# padsSMD.net
KiCad netlist of a schematic drawn in EAGLE
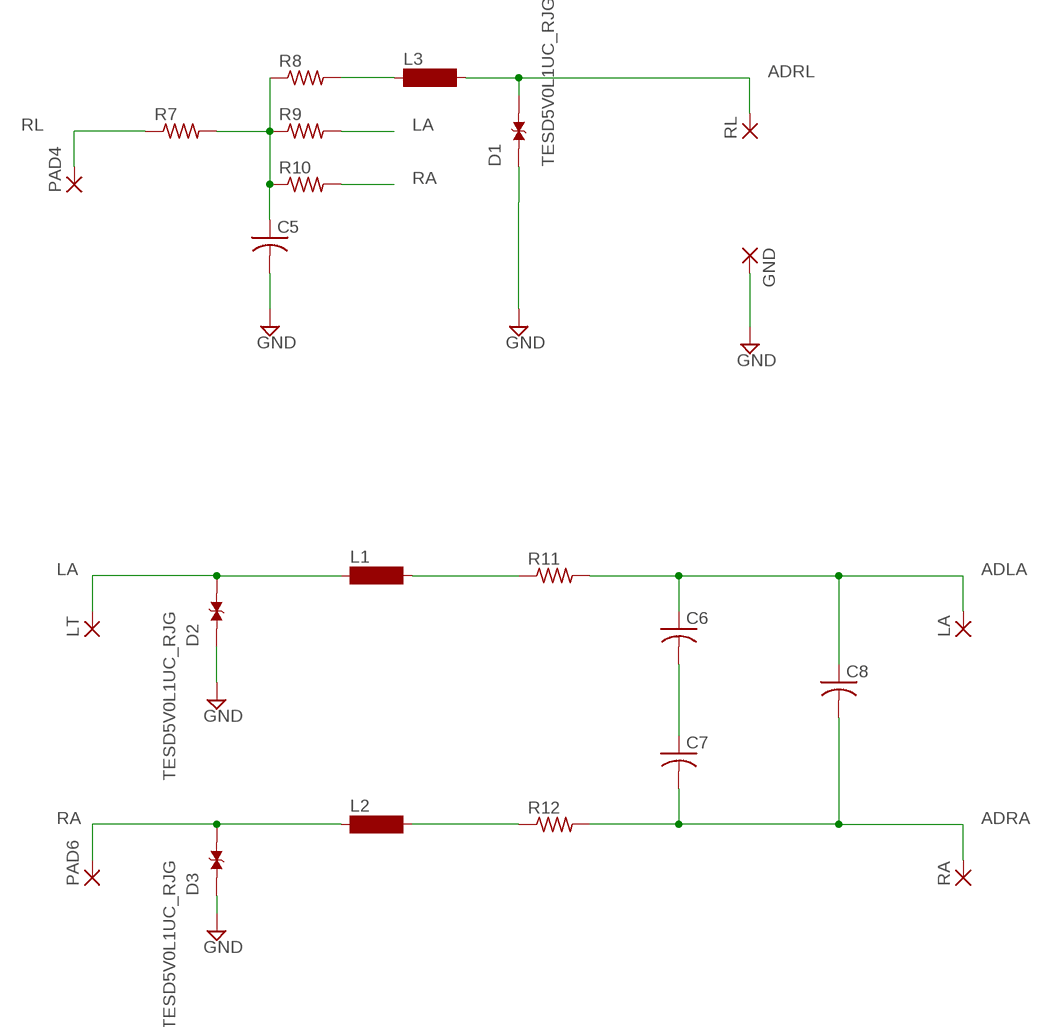
[diagram p0: schematic, sheet 1]

(export (version "E")
  (design (tool "Eeschema 10.0.6"))
  (components
    (comp (ref "C5")
      (value "C-USC1206")
      (footprint "eagle-import:C1206")
      (libsource (lib "eagle-import") (part "C-USC1206"))
    )
    (comp (ref "C6")
      (value "C-USC1206")
      (footprint "eagle-import:C1206")
      (libsource (lib "eagle-import") (part "C-USC1206"))
    )
    (comp (ref "C7")
      (value "C-USC1206")
      (footprint "eagle-import:C1206")
      (libsource (lib "eagle-import") (part "C-USC1206"))
    )
    (comp (ref "C8")
      (value "C-USC1206")
      (footprint "eagle-import:C1206")
      (libsource (lib "eagle-import") (part "C-USC1206"))
    )
    (comp (ref "D1")
      (value "TESD5V0L1UC_RJG")
      (footprint "eagle-import:DIO_TESD5V0L1UC_RJG")
      (fields (field (name "MF") "Taiwan Semiconductor Corporation") (field (name "MP") "TESD5V0L1UC RJG"))
      (libsource (lib "eagle-import") (part "TESD5V0L1UC_RJG"))
    )
    (comp (ref "D2")
      (value "TESD5V0L1UC_RJG")
      (footprint "eagle-import:DIO_TESD5V0L1UC_RJG")
      (fields (field (name "MF") "Taiwan Semiconductor Corporation") (field (name "MP") "TESD5V0L1UC RJG"))
      (libsource (lib "eagle-import") (part "TESD5V0L1UC_RJG"))
    )
    (comp (ref "D3")
      (value "TESD5V0L1UC_RJG")
      (footprint "eagle-import:DIO_TESD5V0L1UC_RJG")
      (fields (field (name "MF") "Taiwan Semiconductor Corporation") (field (name "MP") "TESD5V0L1UC RJG"))
      (libsource (lib "eagle-import") (part "TESD5V0L1UC_RJG"))
    )
    (comp (ref "GND")
      (value "2,15/1,0")
      (footprint "eagle-import:2,15_1,0")
      (libsource (lib "eagle-import") (part "2,15/1,0"))
    )
    (comp (ref "L1")
      (value "SM-1206")
      (footprint "eagle-import:SM-1206")
      (libsource (lib "eagle-import") (part "SM-1206"))
    )
    (comp (ref "L2")
      (value "SM-1206")
      (footprint "eagle-import:SM-1206")
      (libsource (lib "eagle-import") (part "SM-1206"))
    )
    (comp (ref "L3")
      (value "SM-1206")
      (footprint "eagle-import:SM-1206")
      (libsource (lib "eagle-import") (part "SM-1206"))
    )
    (comp (ref "LA")
      (value "2,15/1,0")
      (footprint "eagle-import:2,15_1,0")
      (libsource (lib "eagle-import") (part "2,15/1,0"))
    )
    (comp (ref "LT")
      (value "SMD5")
      (footprint "eagle-import:SMD2,54-5,08")
      (libsource (lib "eagle-import") (part "SMD5"))
    )
    (comp (ref "PAD4")
      (value "SMD5")
      (footprint "eagle-import:SMD2,54-5,08")
      (libsource (lib "eagle-import") (part "SMD5"))
    )
    (comp (ref "PAD6")
      (value "SMD5")
      (footprint "eagle-import:SMD2,54-5,08")
      (libsource (lib "eagle-import") (part "SMD5"))
    )
    (comp (ref "R7")
      (value "R-US_R1206")
      (footprint "eagle-import:R1206")
      (libsource (lib "eagle-import") (part "R-US_R1206"))
    )
    (comp (ref "R8")
      (value "R-US_R1206")
      (footprint "eagle-import:R1206")
      (libsource (lib "eagle-import") (part "R-US_R1206"))
    )
    (comp (ref "R9")
      (value "R-US_R1206")
      (footprint "eagle-import:R1206")
      (libsource (lib "eagle-import") (part "R-US_R1206"))
    )
    (comp (ref "R10")
      (value "R-US_R1206")
      (footprint "eagle-import:R1206")
      (libsource (lib "eagle-import") (part "R-US_R1206"))
    )
    (comp (ref "R11")
      (value "R-US_R1206")
      (footprint "eagle-import:R1206")
      (libsource (lib "eagle-import") (part "R-US_R1206"))
    )
    (comp (ref "R12")
      (value "R-US_R1206")
      (footprint "eagle-import:R1206")
      (libsource (lib "eagle-import") (part "R-US_R1206"))
    )
    (comp (ref "RA")
      (value "2,15/1,0")
      (footprint "eagle-import:2,15_1,0")
      (libsource (lib "eagle-import") (part "2,15/1,0"))
    )
    (comp (ref "RL")
      (value "2,15/1,0")
      (footprint "eagle-import:2,15_1,0")
      (libsource (lib "eagle-import") (part "2,15/1,0"))
    )
  )
  (nets
    (net (code "1") (name "/ADLA") (class "Default")
      (node (ref "C6") (pin "1") (pinfunction "1_1") (pintype "passive"))
      (node (ref "C8") (pin "1") (pinfunction "1_1") (pintype "passive"))
      (node (ref "LA") (pin "1") (pinfunction "P_1") (pintype "passive"))
      (node (ref "R11") (pin "2") (pinfunction "2_2") (pintype "passive"))
    )
    (net (code "2") (name "/ADRA") (class "Default")
      (node (ref "C7") (pin "2") (pinfunction "2_2") (pintype "passive"))
      (node (ref "C8") (pin "2") (pinfunction "2_2") (pintype "passive"))
      (node (ref "R12") (pin "2") (pinfunction "2_2") (pintype "passive"))
      (node (ref "RA") (pin "1") (pinfunction "P_1") (pintype "passive"))
    )
    (net (code "3") (name "/ADRL") (class "Default")
      (node (ref "D1") (pin "2") (pinfunction "2_2") (pintype "passive"))
      (node (ref "L3") (pin "2") (pinfunction "2_2") (pintype "passive"))
      (node (ref "RL") (pin "1") (pinfunction "P_1") (pintype "passive"))
    )
    (net (code "4") (name "/LA") (class "Default")
      (node (ref "D2") (pin "2") (pinfunction "2_2") (pintype "passive"))
      (node (ref "L1") (pin "1") (pinfunction "1_1") (pintype "passive"))
      (node (ref "LT") (pin "1") (pinfunction "P_1") (pintype "passive"))
      (node (ref "R9") (pin "2") (pinfunction "2_2") (pintype "passive"))
    )
    (net (code "5") (name "/RA") (class "Default")
      (node (ref "D3") (pin "2") (pinfunction "2_2") (pintype "passive"))
      (node (ref "L2") (pin "1") (pinfunction "1_1") (pintype "passive"))
      (node (ref "PAD6") (pin "1") (pinfunction "P_1") (pintype "passive"))
      (node (ref "R10") (pin "2") (pinfunction "2_2") (pintype "passive"))
    )
    (net (code "6") (name "/RL") (class "Default")
      (node (ref "PAD4") (pin "1") (pinfunction "P_1") (pintype "passive"))
      (node (ref "R7") (pin "1") (pinfunction "1_1") (pintype "passive"))
    )
    (net (code "7") (name "GND") (class "Default")
      (node (ref "C5") (pin "2") (pinfunction "2_2") (pintype "passive"))
      (node (ref "D1") (pin "1") (pinfunction "1_1") (pintype "passive"))
      (node (ref "D2") (pin "1") (pinfunction "1_1") (pintype "passive"))
      (node (ref "D3") (pin "1") (pinfunction "1_1") (pintype "passive"))
      (node (ref "GND") (pin "1") (pinfunction "P_1") (pintype "passive"))
    )
    (net (code "8") (name "Net-(C5-Pad1)") (class "Default")
      (node (ref "C5") (pin "1") (pinfunction "1_1") (pintype "passive"))
      (node (ref "R10") (pin "1") (pinfunction "1_1") (pintype "passive"))
      (node (ref "R7") (pin "2") (pinfunction "2_2") (pintype "passive"))
      (node (ref "R8") (pin "1") (pinfunction "1_1") (pintype "passive"))
      (node (ref "R9") (pin "1") (pinfunction "1_1") (pintype "passive"))
    )
    (net (code "9") (name "Net-(C6-Pad2)") (class "Default")
      (node (ref "C6") (pin "2") (pinfunction "2_2") (pintype "passive"))
      (node (ref "C7") (pin "1") (pinfunction "1_1") (pintype "passive"))
    )
    (net (code "10") (name "Net-(L1-Pad2)") (class "Default")
      (node (ref "L1") (pin "2") (pinfunction "2_2") (pintype "passive"))
      (node (ref "R11") (pin "1") (pinfunction "1_1") (pintype "passive"))
    )
    (net (code "11") (name "Net-(L2-Pad2)") (class "Default")
      (node (ref "L2") (pin "2") (pinfunction "2_2") (pintype "passive"))
      (node (ref "R12") (pin "1") (pinfunction "1_1") (pintype "passive"))
    )
    (net (code "12") (name "Net-(L3-Pad1)") (class "Default")
      (node (ref "L3") (pin "1") (pinfunction "1_1") (pintype "passive"))
      (node (ref "R8") (pin "2") (pinfunction "2_2") (pintype "passive"))
    )
  )
)
